# ATTiny2313_ISP.net
KiCad netlist of a schematic drawn in EAGLE
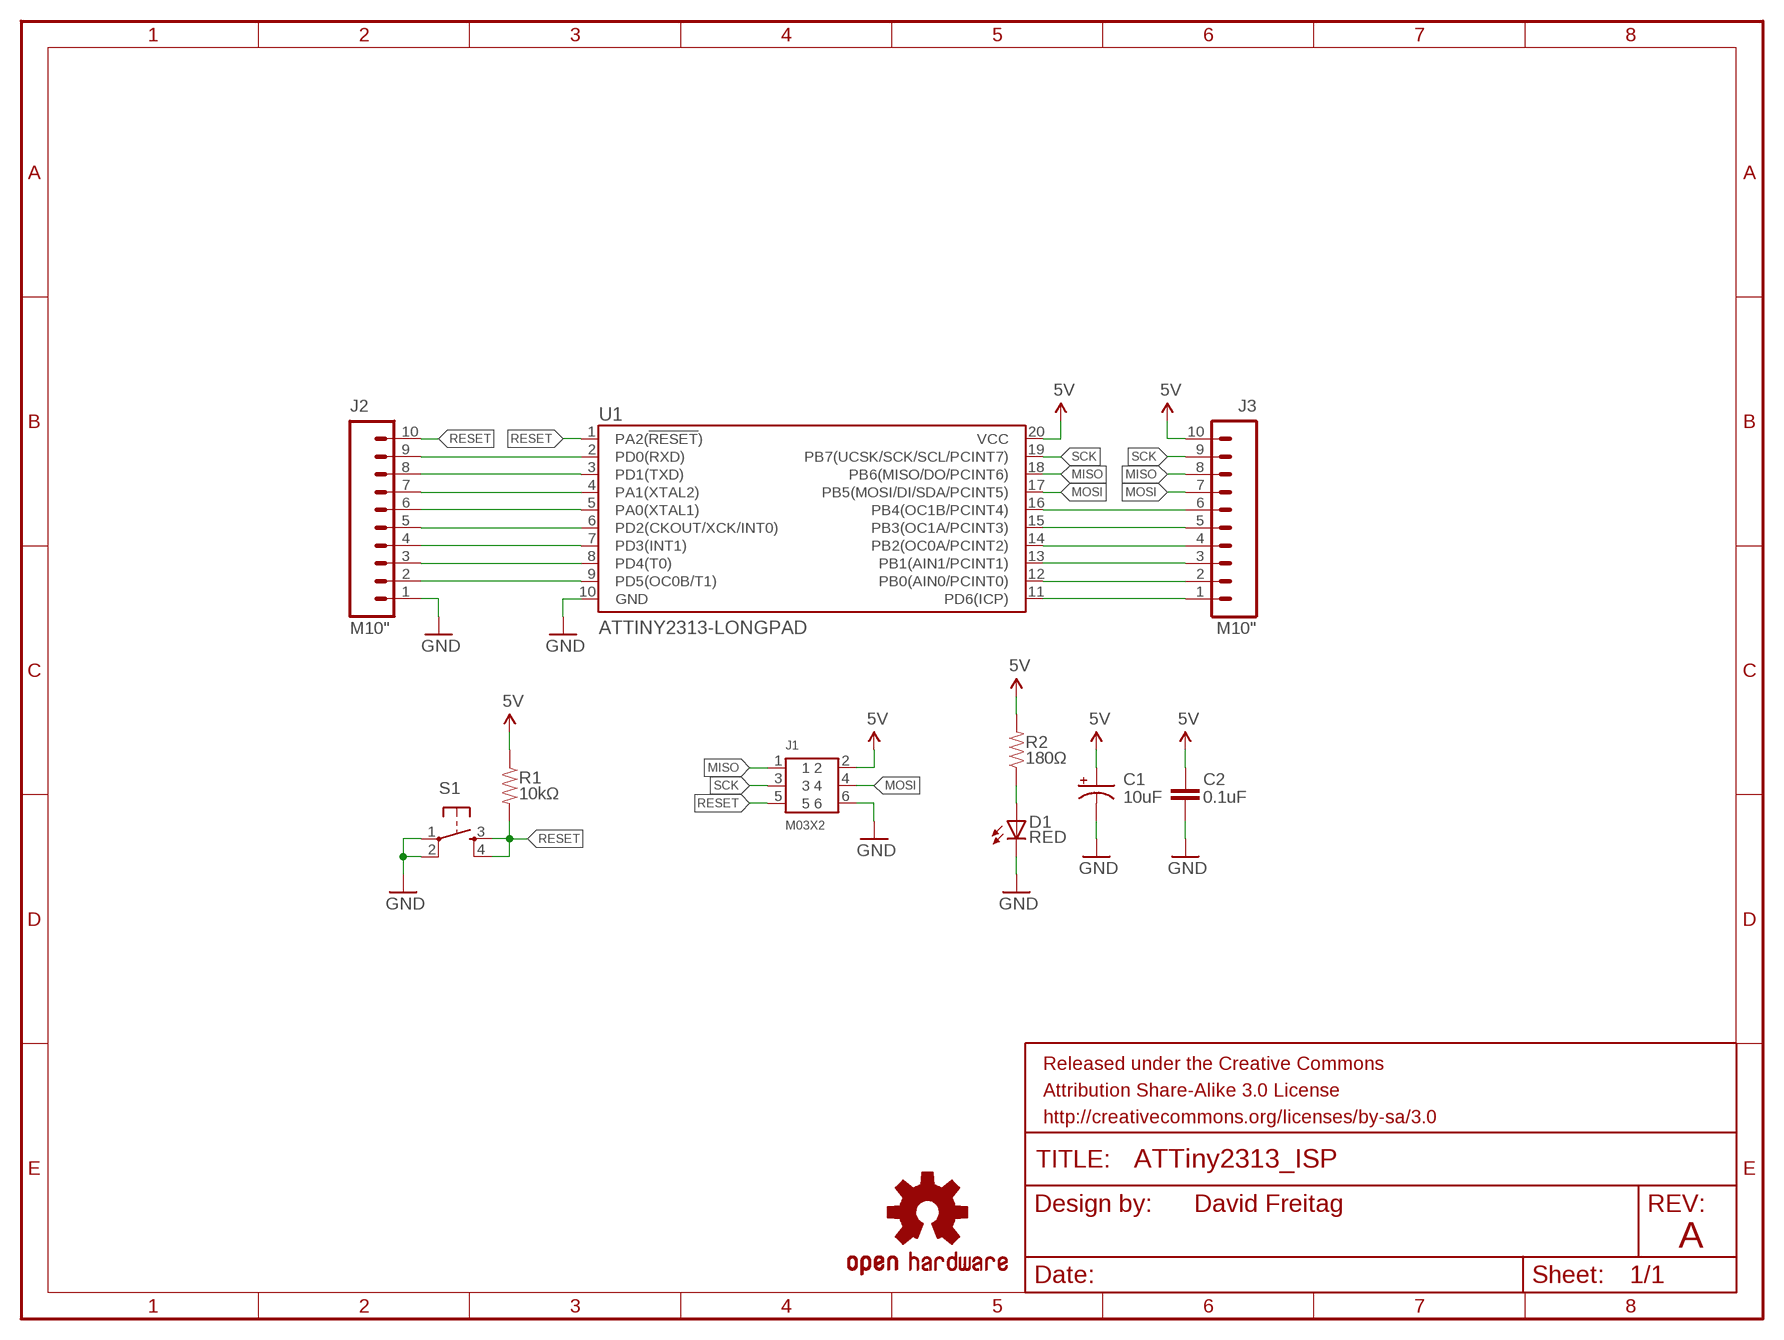
[diagram p0: schematic, sheet 1]

(export (version "E")
  (design (tool "Eeschema 10.0.6"))
  (components
    (comp (ref "C1")
      (value "10uF")
      (footprint "eagle-import:CPOL-RADIAL-10UF-25V")
      (libsource (lib "eagle-import") (part "CAP_POLPTH2"))
    )
    (comp (ref "C2")
      (value "0.1uF")
      (footprint "eagle-import:CAP-PTH-SMALLEZ")
      (libsource (lib "eagle-import") (part "CAPEZ"))
    )
    (comp (ref "D1")
      (value "RED")
      (footprint "eagle-import:LED3MM")
      (libsource (lib "eagle-import") (part "LED3MM"))
    )
    (comp (ref "FRAME1")
      (value "FRAME-LETTER")
      (footprint "eagle-import:CREATIVE_COMMONS")
      (libsource (lib "eagle-import") (part "FRAME-LETTER"))
    )
    (comp (ref "J1")
      (value "M03X2")
      (footprint "eagle-import:M03X2")
      (libsource (lib "eagle-import") (part "M03X2"))
    )
    (comp (ref "J2")
      (value "M10\"")
      (footprint "eagle-import:1X10")
      (libsource (lib "eagle-import") (part "M10{dblquote}"))
    )
    (comp (ref "J3")
      (value "M10\"")
      (footprint "eagle-import:1X10")
      (libsource (lib "eagle-import") (part "M10{dblquote}"))
    )
    (comp (ref "LOGO1")
      (value "OSHW-LOGOM")
      (footprint "eagle-import:OSHW-LOGO-M")
      (libsource (lib "eagle-import") (part "OSHW-LOGOM"))
    )
    (comp (ref "R1")
      (value "10kΩ")
      (footprint "eagle-import:AXIAL-0.2")
      (libsource (lib "eagle-import") (part "RESISTORPTH-1/8W"))
    )
    (comp (ref "R2")
      (value "180Ω")
      (footprint "eagle-import:AXIAL-0.2")
      (libsource (lib "eagle-import") (part "RESISTORPTH-1/8W"))
    )
    (comp (ref "S1")
      (value "TAC_SWITCHPTH")
      (footprint "eagle-import:TACTILE-PTH")
      (libsource (lib "eagle-import") (part "TAC_SWITCHPTH"))
    )
    (comp (ref "U1")
      (value "ATTINY2313-LONGPAD")
      (footprint "eagle-import:DIP20-LONGPAD")
      (libsource (lib "eagle-import") (part "ATTINY2313-LONGPAD"))
    )
  )
  (nets
    (net (code "1") (name "5V") (class "Default")
      (node (ref "C1") (pin "1") (pinfunction "+_1") (pintype "passive"))
      (node (ref "C2") (pin "1") (pinfunction "1_1") (pintype "passive"))
      (node (ref "J1") (pin "2") (pinfunction "2_2") (pintype "bidirectional"))
      (node (ref "J3") (pin "10") (pinfunction "10_10") (pintype "passive"))
      (node (ref "R1") (pin "P$1") (pinfunction "1_P$1") (pintype "passive"))
      (node (ref "R2") (pin "P$2") (pinfunction "2_P$2") (pintype "passive"))
      (node (ref "U1") (pin "20") (pinfunction "VCC_20") (pintype "bidirectional"))
    )
    (net (code "2") (name "GND") (class "Default")
      (node (ref "C1") (pin "2") (pinfunction "-_2") (pintype "passive"))
      (node (ref "C2") (pin "2") (pinfunction "2_2") (pintype "passive"))
      (node (ref "D1") (pin "K") (pinfunction "C_K") (pintype "passive"))
      (node (ref "J1") (pin "6") (pinfunction "6_6") (pintype "bidirectional"))
      (node (ref "J2") (pin "1") (pinfunction "1_1") (pintype "passive"))
      (node (ref "S1") (pin "1") (pinfunction "1_1") (pintype "passive"))
      (node (ref "S1") (pin "2") (pinfunction "2_2") (pintype "passive"))
      (node (ref "U1") (pin "10") (pinfunction "GND_10") (pintype "bidirectional"))
    )
    (net (code "3") (name "MISO") (class "Default")
      (node (ref "J1") (pin "1") (pinfunction "1_1") (pintype "bidirectional"))
      (node (ref "J3") (pin "8") (pinfunction "8_8") (pintype "passive"))
      (node (ref "U1") (pin "18") (pinfunction "PB6(MISO/DO/PCINT6)_18") (pintype "bidirectional"))
    )
    (net (code "4") (name "MOSI") (class "Default")
      (node (ref "J1") (pin "4") (pinfunction "4_4") (pintype "bidirectional"))
      (node (ref "J3") (pin "7") (pinfunction "7_7") (pintype "passive"))
      (node (ref "U1") (pin "17") (pinfunction "PB5(MOSI/DI/SDA/PCINT5)_17") (pintype "bidirectional"))
    )
    (net (code "5") (name "Net-(R2-1)") (class "Default")
      (node (ref "D1") (pin "A") (pinfunction "A_A") (pintype "passive"))
      (node (ref "R2") (pin "P$1") (pinfunction "1_P$1") (pintype "passive"))
    )
    (net (code "6") (name "Net-(U1-PA0(XTAL1))") (class "Default")
      (node (ref "J2") (pin "6") (pinfunction "6_6") (pintype "passive"))
      (node (ref "U1") (pin "5") (pinfunction "PA0(XTAL1)_5") (pintype "bidirectional"))
    )
    (net (code "7") (name "Net-(U1-PA1(XTAL2))") (class "Default")
      (node (ref "J2") (pin "7") (pinfunction "7_7") (pintype "passive"))
      (node (ref "U1") (pin "4") (pinfunction "PA1(XTAL2)_4") (pintype "bidirectional"))
    )
    (net (code "8") (name "Net-(U1-PB0(AIN0{slash}PCINT0))") (class "Default")
      (node (ref "J3") (pin "2") (pinfunction "2_2") (pintype "passive"))
      (node (ref "U1") (pin "12") (pinfunction "PB0(AIN0/PCINT0)_12") (pintype "bidirectional"))
    )
    (net (code "9") (name "Net-(U1-PB1(AIN1{slash}PCINT1))") (class "Default")
      (node (ref "J3") (pin "3") (pinfunction "3_3") (pintype "passive"))
      (node (ref "U1") (pin "13") (pinfunction "PB1(AIN1/PCINT1)_13") (pintype "bidirectional"))
    )
    (net (code "10") (name "Net-(U1-PB2(OC0A{slash}PCINT2))") (class "Default")
      (node (ref "J3") (pin "4") (pinfunction "4_4") (pintype "passive"))
      (node (ref "U1") (pin "14") (pinfunction "PB2(OC0A/PCINT2)_14") (pintype "bidirectional"))
    )
    (net (code "11") (name "Net-(U1-PB3(OC1A{slash}PCINT3))") (class "Default")
      (node (ref "J3") (pin "5") (pinfunction "5_5") (pintype "passive"))
      (node (ref "U1") (pin "15") (pinfunction "PB3(OC1A/PCINT3)_15") (pintype "bidirectional"))
    )
    (net (code "12") (name "Net-(U1-PB4(OC1B{slash}PCINT4))") (class "Default")
      (node (ref "J3") (pin "6") (pinfunction "6_6") (pintype "passive"))
      (node (ref "U1") (pin "16") (pinfunction "PB4(OC1B/PCINT4)_16") (pintype "bidirectional"))
    )
    (net (code "13") (name "Net-(U1-PD0(RXD))") (class "Default")
      (node (ref "J2") (pin "9") (pinfunction "9_9") (pintype "passive"))
      (node (ref "U1") (pin "2") (pinfunction "PD0(RXD)_2") (pintype "bidirectional"))
    )
    (net (code "14") (name "Net-(U1-PD1(TXD))") (class "Default")
      (node (ref "J2") (pin "8") (pinfunction "8_8") (pintype "passive"))
      (node (ref "U1") (pin "3") (pinfunction "PD1(TXD)_3") (pintype "bidirectional"))
    )
    (net (code "15") (name "Net-(U1-PD2(CKOUT{slash}XCK{slash}INT0))") (class "Default")
      (node (ref "J2") (pin "5") (pinfunction "5_5") (pintype "passive"))
      (node (ref "U1") (pin "6") (pinfunction "PD2(CKOUT/XCK/INT0)_6") (pintype "bidirectional"))
    )
    (net (code "16") (name "Net-(U1-PD3(INT1))") (class "Default")
      (node (ref "J2") (pin "4") (pinfunction "4_4") (pintype "passive"))
      (node (ref "U1") (pin "7") (pinfunction "PD3(INT1)_7") (pintype "bidirectional"))
    )
    (net (code "17") (name "Net-(U1-PD4(T0))") (class "Default")
      (node (ref "J2") (pin "3") (pinfunction "3_3") (pintype "passive"))
      (node (ref "U1") (pin "8") (pinfunction "PD4(T0)_8") (pintype "bidirectional"))
    )
    (net (code "18") (name "Net-(U1-PD5(OC0B{slash}T1))") (class "Default")
      (node (ref "J2") (pin "2") (pinfunction "2_2") (pintype "passive"))
      (node (ref "U1") (pin "9") (pinfunction "PD5(OC0B/T1)_9") (pintype "bidirectional"))
    )
    (net (code "19") (name "Net-(U1-PD6(ICP))") (class "Default")
      (node (ref "J3") (pin "1") (pinfunction "1_1") (pintype "passive"))
      (node (ref "U1") (pin "11") (pinfunction "PD6(ICP)_11") (pintype "bidirectional"))
    )
    (net (code "20") (name "RESET") (class "Default")
      (node (ref "J1") (pin "5") (pinfunction "5_5") (pintype "bidirectional"))
      (node (ref "J2") (pin "10") (pinfunction "10_10") (pintype "passive"))
      (node (ref "R1") (pin "P$2") (pinfunction "2_P$2") (pintype "passive"))
      (node (ref "S1") (pin "3") (pinfunction "3_3") (pintype "passive"))
      (node (ref "S1") (pin "4") (pinfunction "4_4") (pintype "passive"))
      (node (ref "U1") (pin "1") (pinfunction "PA2(~{RESET})_1") (pintype "bidirectional"))
    )
    (net (code "21") (name "SCK") (class "Default")
      (node (ref "J1") (pin "3") (pinfunction "3_3") (pintype "bidirectional"))
      (node (ref "J3") (pin "9") (pinfunction "9_9") (pintype "passive"))
      (node (ref "U1") (pin "19") (pinfunction "PB7(UCSK/SCK/SCL/PCINT7)_19") (pintype "bidirectional"))
    )
  )
)
